# Fast_PLL_Page_2.net
KiCad netlist of a schematic drawn in Altium Designer
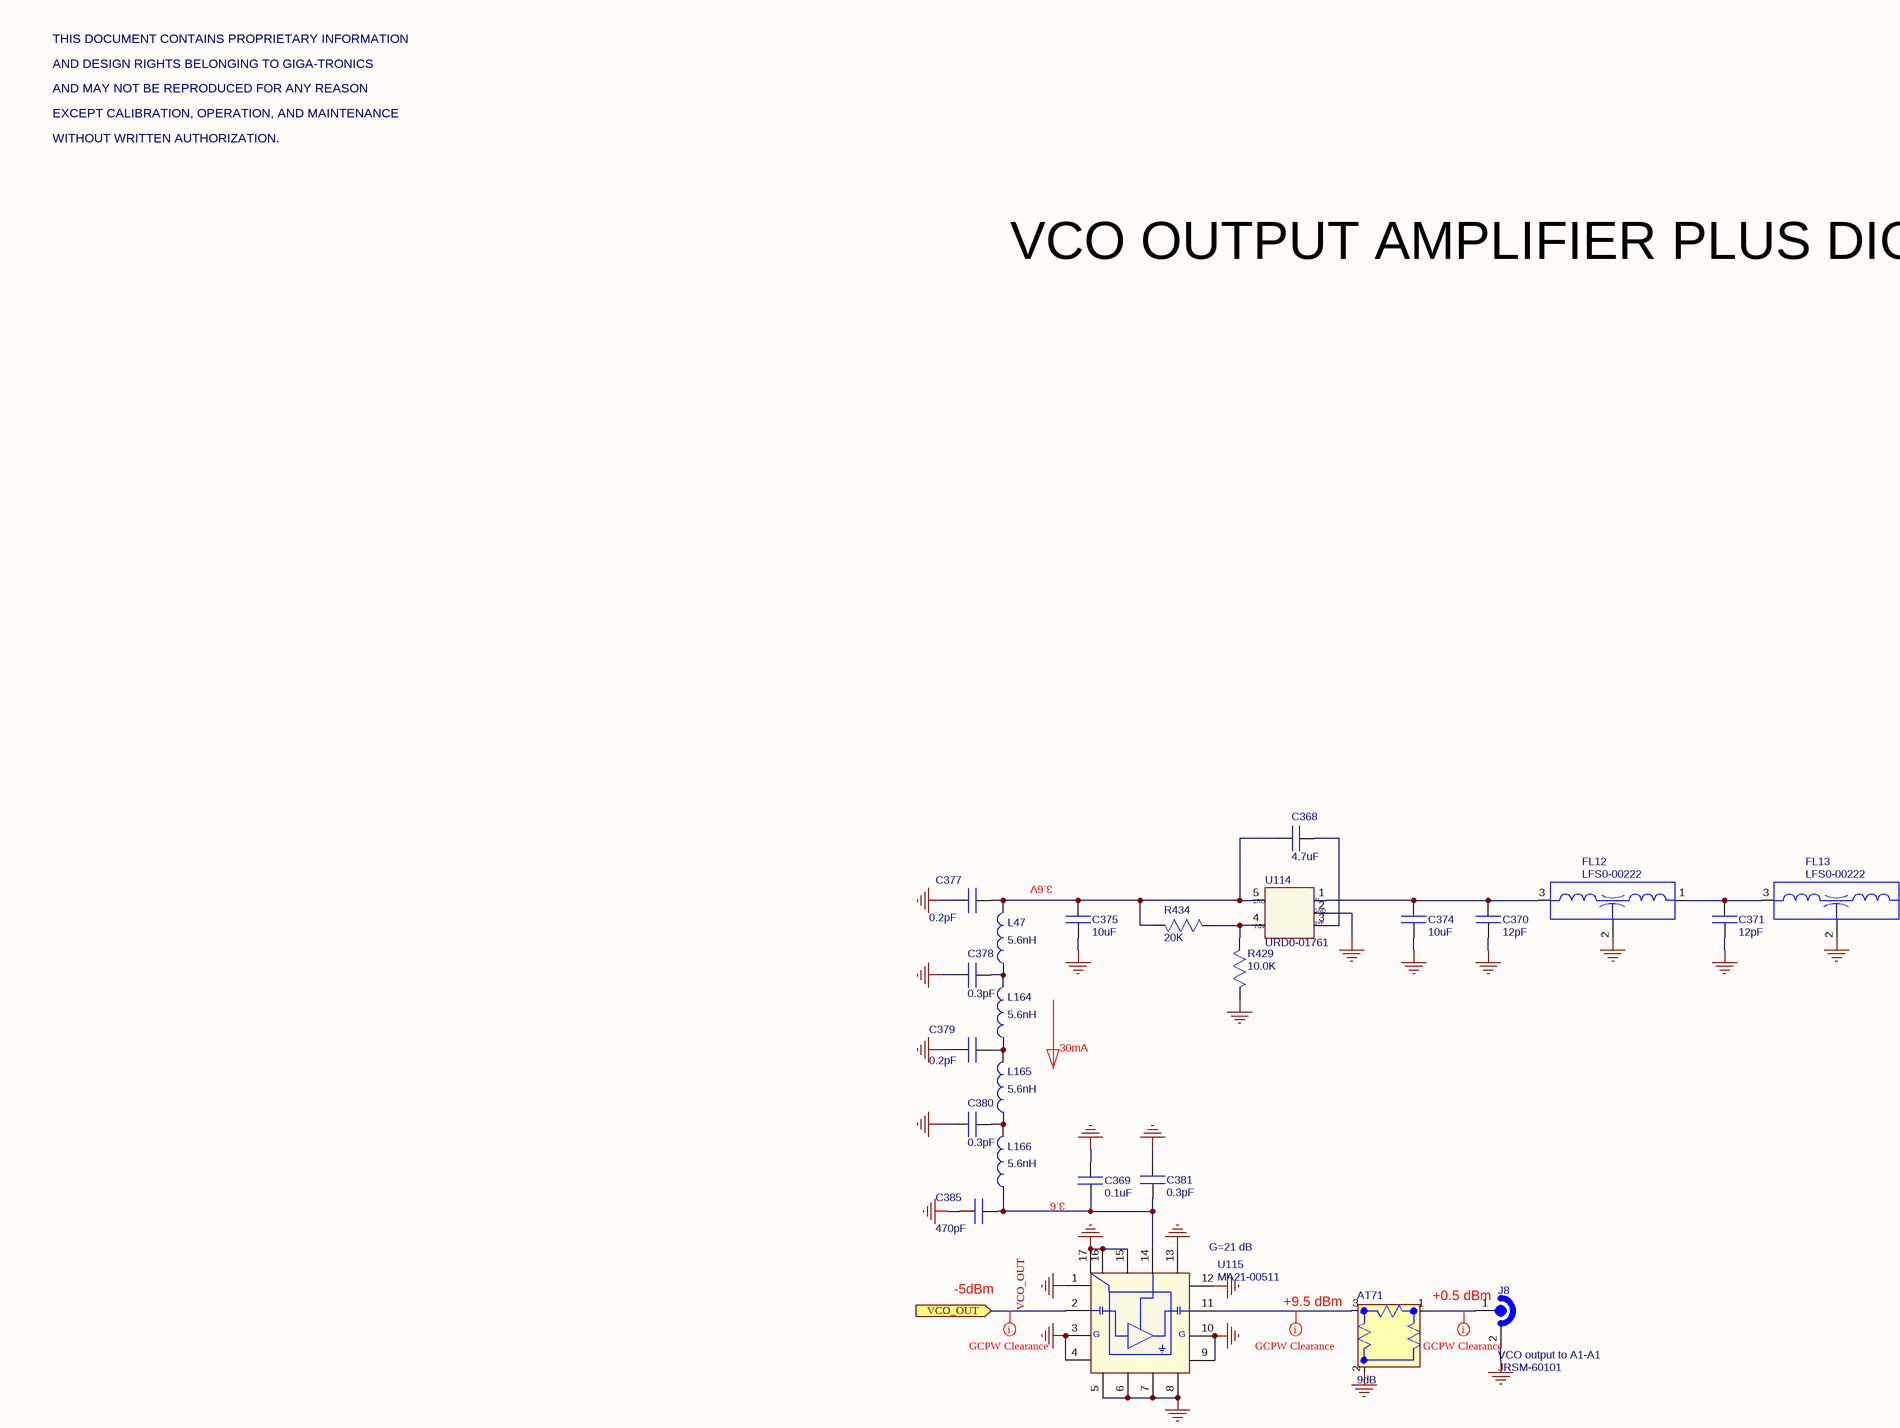
[diagram p0: Fast PLL Page 2.SchDoc, top left]
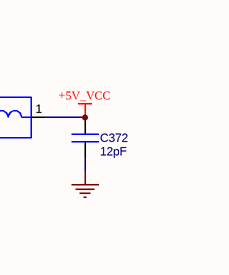
[diagram p1: Fast PLL Page 2.SchDoc, top right]
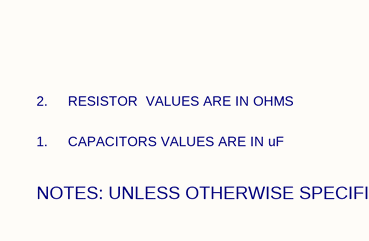
[diagram p2: Fast PLL Page 2.SchDoc, bottom left]
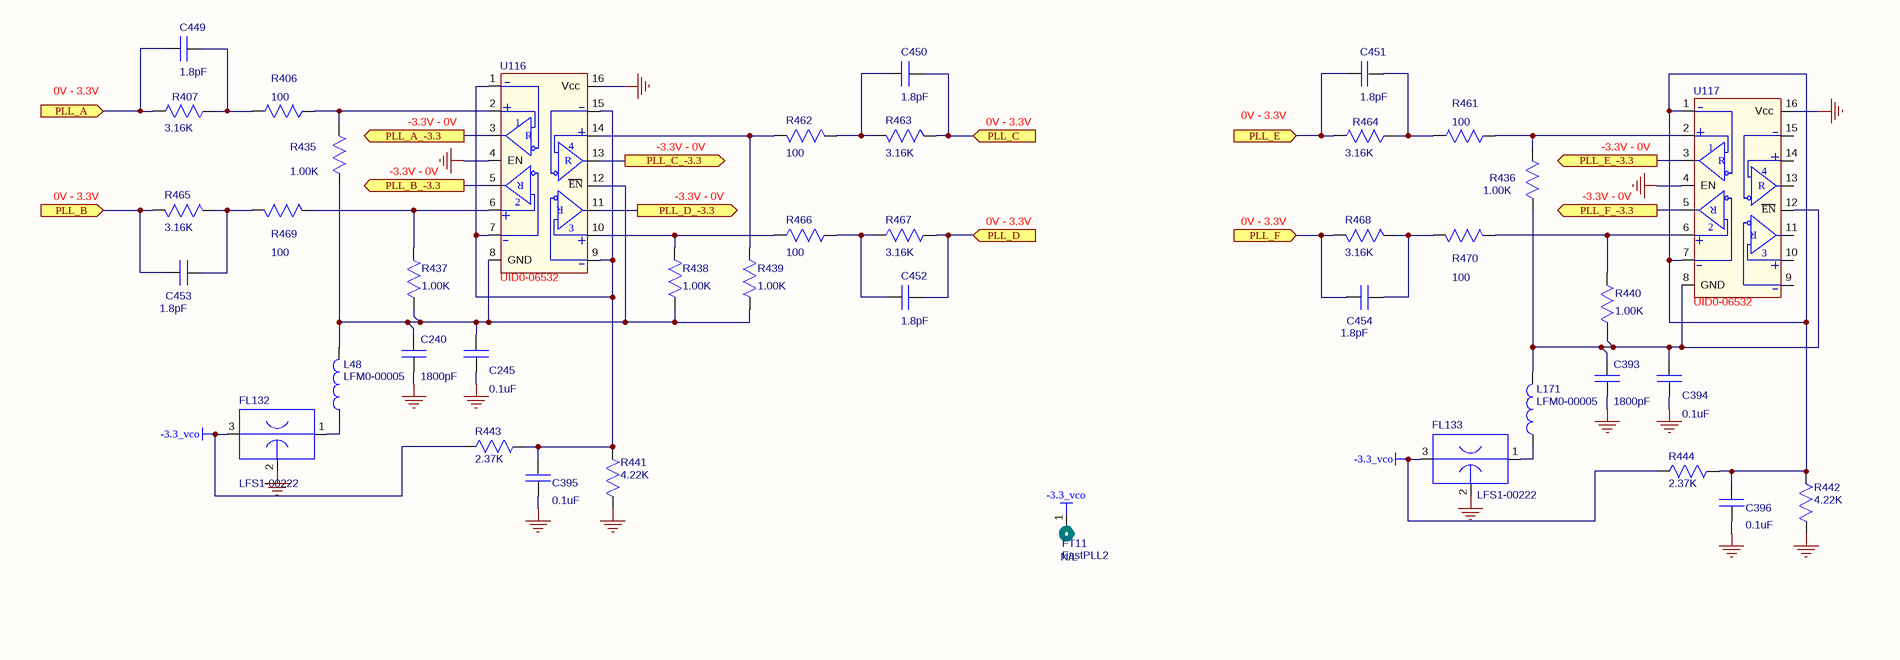
[diagram p3: Fast PLL Page 2.SchDoc, bottom right]

(export (version "E")
  (design (tool "Eeschema 10.0.6"))
  (components
    (comp (ref "AT71")
      (value "9dB")
      (footprint "ATTN-IMS-0805")
      (description "PAD;CHIP;9dB;+/-.3dB;.08 x .05;50 OHM;FACE DOWN")
      (fields (field (name "APPROVED") "CL"))
      (libsource (lib "Giga-tronics") (part "MPFC-A1009"))
    )
    (comp (ref "C240")
      (value "1800pF")
      (footprint "CAP-0402-N")
      (description "1800 PF;5%;X7R>50V;CHIP;0402")
      (fields (field (name "APPROVED") "CL"))
      (libsource (lib "Giga-tronics") (part "CK40-02180"))
    )
    (comp (ref "C245")
      (value "0.1uF")
      (footprint "CAP-0603-H035-N")
      (description ".1UF;10%;X7R;16V;CHIP;0603")
      (fields (field (name "APPROVED") "CL"))
      (libsource (lib "Giga-tronics") (part "CK45-04100"))
    )
    (comp (ref "C368")
      (value "4.7uF")
      (footprint "CAP-0805-N")
      (description "4.7uF 25V X5R CHIP CERAMIC")
      (fields (field (name "APPROVED") "CL"))
      (libsource (lib "Giga-tronics") (part "CK50-15470"))
    )
    (comp (ref "C369")
      (value "0.1uF")
      (footprint "CAP-0402-N")
      (description ".1 UF,10%;X7R;16V,CHIP;0402")
      (fields (field (name "APPROVED") "CL"))
      (libsource (lib "Giga-tronics") (part "CK40-04100"))
    )
    (comp (ref "C370")
      (value "12pF")
      (footprint "CAP-0402-N")
      (description "12 PF;5%;COG;>50V;CHIP;0402")
      (fields (field (name "APPROVED") "CL"))
      (libsource (lib "Giga-tronics") (part "CK40-00120"))
    )
    (comp (ref "C371")
      (value "12pF")
      (footprint "CAP-0402-N")
      (description "12 PF;5%;COG;>50V;CHIP;0402")
      (fields (field (name "APPROVED") "CL"))
      (libsource (lib "Giga-tronics") (part "CK40-00120"))
    )
    (comp (ref "C372")
      (value "12pF")
      (footprint "CAP-0402-N")
      (description "12 PF;5%;COG;>50V;CHIP;0402")
      (fields (field (name "APPROVED") "CL"))
      (libsource (lib "Giga-tronics") (part "CK40-00120"))
    )
    (comp (ref "C374")
      (value "10uF")
      (footprint "CAP-0805-N")
      (description "10uF 16V X5R CHIP CERAMIC")
      (fields (field (name "APPROVED") "CL"))
      (libsource (lib "Giga-tronics") (part "CK50-06100"))
    )
    (comp (ref "C375")
      (value "10uF")
      (footprint "CAP-0805-N")
      (description "10uF 16V X5R CHIP CERAMIC")
      (fields (field (name "APPROVED") "CL"))
      (libsource (lib "Giga-tronics") (part "CK50-06100"))
    )
    (comp (ref "C377")
      (value "0.2pF")
      (footprint "CAP-0402-RF")
      (description ".2 PF;200V;.05PF;HIGH Q;SMT;CERAMIC;0402")
      (fields (field (name "APPROVED") "CL"))
      (libsource (lib "Giga-tronics") (part "CK41-00002"))
    )
    (comp (ref "C378")
      (value "0.3pF")
      (footprint "CAP-0402-RF")
      (description ".3 PF 200V .05PF HIGH Q SMT 0402")
      (fields (field (name "APPROVED") "CL"))
      (libsource (lib "Giga-tronics") (part "CK41-00003"))
    )
    (comp (ref "C379")
      (value "0.2pF")
      (footprint "CAP-0402-RF")
      (description ".2 PF;200V;.05PF;HIGH Q;SMT;CERAMIC;0402")
      (fields (field (name "APPROVED") "CL"))
      (libsource (lib "Giga-tronics") (part "CK41-00002"))
    )
    (comp (ref "C380")
      (value "0.3pF")
      (footprint "CAP-0402-RF")
      (description ".3 PF 200V .05PF HIGH Q SMT 0402")
      (fields (field (name "APPROVED") "CL"))
      (libsource (lib "Giga-tronics") (part "CK41-00003"))
    )
    (comp (ref "C381")
      (value "0.3pF")
      (footprint "CAP-0402-RF")
      (description ".3 PF 200V .05PF HIGH Q SMT 0402")
      (fields (field (name "APPROVED") "CL"))
      (libsource (lib "Giga-tronics") (part "CK41-00003"))
    )
    (comp (ref "C385")
      (value "470pF")
      (footprint "CAP-0402-N")
      (description "470 PF;5%;COG;>50V;CHIP;0402")
      (fields (field (name "APPROVED") "CL"))
      (libsource (lib "Giga-tronics") (part "CK40-01470"))
    )
    (comp (ref "C393")
      (value "1800pF")
      (footprint "CAP-0402-N")
      (description "1800 PF;5%;X7R>50V;CHIP;0402")
      (fields (field (name "APPROVED") "CL"))
      (libsource (lib "Giga-tronics") (part "CK40-02180"))
    )
    (comp (ref "C394")
      (value "0.1uF")
      (footprint "CAP-0603-H035-N")
      (description ".1UF;10%;X7R;16V;CHIP;0603")
      (fields (field (name "APPROVED") "CL"))
      (libsource (lib "Giga-tronics") (part "CK45-04100"))
    )
    (comp (ref "C395")
      (value "0.1uF")
      (footprint "CAP-0603-H035-N")
      (description ".1UF;10%;X7R;16V;CHIP;0603")
      (fields (field (name "APPROVED") "CL"))
      (libsource (lib "Giga-tronics") (part "CK45-04100"))
    )
    (comp (ref "C396")
      (value "0.1uF")
      (footprint "CAP-0603-H035-N")
      (description ".1UF;10%;X7R;16V;CHIP;0603")
      (fields (field (name "APPROVED") "CL"))
      (libsource (lib "Giga-tronics") (part "CK45-04100"))
    )
    (comp (ref "C449")
      (value "1.8pF")
      (footprint "CAP-0402-N")
      (description "1.8pF;5%;COG;50V;CHIP;0402")
      (fields (field (name "APPROVED") "NM"))
      (libsource (lib "Giga-tronics") (part "CK40-00018"))
    )
    (comp (ref "C450")
      (value "1.8pF")
      (footprint "CAP-0402-N")
      (description "1.8pF;5%;COG;50V;CHIP;0402")
      (fields (field (name "APPROVED") "NM"))
      (libsource (lib "Giga-tronics") (part "CK40-00018"))
    )
    (comp (ref "C451")
      (value "1.8pF")
      (footprint "CAP-0402-N")
      (description "1.8pF;5%;COG;50V;CHIP;0402")
      (fields (field (name "APPROVED") "NM"))
      (libsource (lib "Giga-tronics") (part "CK40-00018"))
    )
    (comp (ref "C452")
      (value "1.8pF")
      (footprint "CAP-0402-N")
      (description "1.8pF;5%;COG;50V;CHIP;0402")
      (fields (field (name "APPROVED") "NM"))
      (libsource (lib "Giga-tronics") (part "CK40-00018"))
    )
    (comp (ref "C453")
      (value "1.8pF")
      (footprint "CAP-0402-N")
      (description "1.8pF;5%;COG;50V;CHIP;0402")
      (fields (field (name "APPROVED") "NM"))
      (libsource (lib "Giga-tronics") (part "CK40-00018"))
    )
    (comp (ref "C454")
      (value "1.8pF")
      (footprint "CAP-0402-N")
      (description "1.8pF;5%;COG;50V;CHIP;0402")
      (fields (field (name "APPROVED") "NM"))
      (libsource (lib "Giga-tronics") (part "CK40-00018"))
    )
    (comp (ref "FL12")
      (value "Filter EMI 2200PF,1206")
      (footprint "FIL-NFE31P-1206-4P")
      (fields (field (name "G_PN") "LFS0-00222") (field (name "APPROVED") "CL"))
      (libsource (lib "Giga-tronics") (part "LFS0-00222"))
    )
    (comp (ref "FL13")
      (value "Filter EMI 2200PF,1206")
      (footprint "FIL-NFE31P-1206-4P")
      (fields (field (name "G_PN") "LFS0-00222") (field (name "APPROVED") "CL"))
      (libsource (lib "Giga-tronics") (part "LFS0-00222"))
    )
    (comp (ref "FL132")
      (value "NFM18CC222R1C3")
      (footprint "FIL-NFL18C")
      (description "2200 PF FEED THRU FILTER 0603")
      (fields (field (name "G_PN") "LFS1-00222") (field (name "APPROVED") "NM"))
      (libsource (lib "Giga-tronics") (part "LFS1-00222"))
    )
    (comp (ref "FL133")
      (value "NFM18CC222R1C3")
      (footprint "FIL-NFL18C")
      (description "2200 PF FEED THRU FILTER 0603")
      (fields (field (name "G_PN") "LFS1-00222") (field (name "APPROVED") "NM"))
      (libsource (lib "Giga-tronics") (part "LFS1-00222"))
    )
    (comp (ref "FT11")
      (value "FastPLL2")
      (footprint "FromToNode_ML2")
      (fields (field (name "NOLOAD") "N/L") (field (name "APPROVED") "*"))
      (libsource (lib "Giga-tronics") (part "FromToNode"))
    )
    (comp (ref "J8")
      (value "VCO output to A1-A1")
      (footprint "JRSM-60101")
      (description "SMPM SM MALE,STRAIGHT SMT, R/A COPLANAR, 4 PIN THRU-HOLE")
      (fields (field (name "G_PN") "JRSM-60101") (field (name "APPROVED") "CL"))
      (libsource (lib "Giga-tronics") (part "JRSM-60101"))
    )
    (comp (ref "L47")
      (value "5.6nH")
      (footprint "IND-0402HP")
      (description "INDUCTOR;5.6NH;2%;6.6GHZ SRF;105Q @1.7GHZ;.048 DCR;1.6A;0402")
      (fields (field (name "APPROVED") "CL"))
      (libsource (lib "Giga-tronics") (part "LSA6-02560"))
    )
    (comp (ref "L48")
      (value "EMI FILTER;CHIP;330 OHMS@100MHZ;0.5A;0.30 DCR;0603")
      (footprint "BLM18A_Murata")
      (fields (field (name "G_PN") "LFM0-00005") (field (name "APPROVED") "NM"))
      (libsource (lib "Giga-tronics") (part "LFM0-00005"))
    )
    (comp (ref "L164")
      (value "5.6nH")
      (footprint "IND-0402HP")
      (description "INDUCTOR;5.6NH;2%;6.6GHZ SRF;105Q @1.7GHZ;.048 DCR;1.6A;0402")
      (fields (field (name "APPROVED") "CL"))
      (libsource (lib "Giga-tronics") (part "LSA6-02560"))
    )
    (comp (ref "L165")
      (value "5.6nH")
      (footprint "IND-0402HP")
      (description "INDUCTOR;5.6NH;2%;6.6GHZ SRF;105Q @1.7GHZ;.048 DCR;1.6A;0402")
      (fields (field (name "APPROVED") "CL"))
      (libsource (lib "Giga-tronics") (part "LSA6-02560"))
    )
    (comp (ref "L166")
      (value "5.6nH")
      (footprint "IND-0402HP")
      (description "INDUCTOR;5.6NH;2%;6.6GHZ SRF;105Q @1.7GHZ;.048 DCR;1.6A;0402")
      (fields (field (name "APPROVED") "CL"))
      (libsource (lib "Giga-tronics") (part "LSA6-02560"))
    )
    (comp (ref "L171")
      (value "EMI FILTER;CHIP;330 OHMS@100MHZ;0.5A;0.30 DCR;0603")
      (footprint "BLM18A_Murata")
      (fields (field (name "G_PN") "LFM0-00005") (field (name "APPROVED") "NM"))
      (libsource (lib "Giga-tronics") (part "LFM0-00005"))
    )
    (comp (ref "R406")
      (value "100")
      (footprint "RES-0402-N")
      (description "100 OHMS; 1%; .1W; 100PPM; FILM; CHIP; 0402")
      (fields (field (name "APPROVED") "CL"))
      (libsource (lib "Giga-tronics") (part "RK35-01000"))
    )
    (comp (ref "R407")
      (value "3.16K")
      (footprint "RES-0402-N")
      (description "3.16K OHMS;.06W;1%;200PPM;FILM;CHIP;0402")
      (fields (field (name "APPROVED") "CL"))
      (libsource (lib "Giga-tronics") (part "RK35-13160"))
    )
    (comp (ref "R429")
      (value "10.0K")
      (footprint "RES-0402-N")
      (description "10.0K OHMS;.06W;1%;200PPM;FILM;CHIP;0402")
      (fields (field (name "APPROVED") "CL"))
      (libsource (lib "Giga-tronics") (part "RK35-21000"))
    )
    (comp (ref "R434")
      (value "20K")
      (footprint "RES-0402-N")
      (description "20K OHMS;.06W;1%;100PPM;FILM;CHIP;0402")
      (fields (field (name "APPROVED") "CL"))
      (libsource (lib "Giga-tronics") (part "RK35-22000"))
    )
    (comp (ref "R435")
      (value "1.00K")
      (footprint "RES-0402-N")
      (description "1.0K OHMS;.06W;1%;200PPM;FILM;CHIP;0402")
      (fields (field (name "APPROVED") "CL"))
      (libsource (lib "Giga-tronics") (part "RK35-11000"))
    )
    (comp (ref "R436")
      (value "1.00K")
      (footprint "RES-0402-N")
      (description "1.0K OHMS;.06W;1%;200PPM;FILM;CHIP;0402")
      (fields (field (name "APPROVED") "CL"))
      (libsource (lib "Giga-tronics") (part "RK35-11000"))
    )
    (comp (ref "R437")
      (value "1.00K")
      (footprint "RES-0402-N")
      (description "1.0K OHMS;.06W;1%;200PPM;FILM;CHIP;0402")
      (fields (field (name "APPROVED") "CL"))
      (libsource (lib "Giga-tronics") (part "RK35-11000"))
    )
    (comp (ref "R438")
      (value "1.00K")
      (footprint "RES-0402-N")
      (description "1.0K OHMS;.06W;1%;200PPM;FILM;CHIP;0402")
      (fields (field (name "APPROVED") "CL"))
      (libsource (lib "Giga-tronics") (part "RK35-11000"))
    )
    (comp (ref "R439")
      (value "1.00K")
      (footprint "RES-0402-N")
      (description "1.0K OHMS;.06W;1%;200PPM;FILM;CHIP;0402")
      (fields (field (name "APPROVED") "CL"))
      (libsource (lib "Giga-tronics") (part "RK35-11000"))
    )
    (comp (ref "R440")
      (value "1.00K")
      (footprint "RES-0402-N")
      (description "1.0K OHMS;.06W;1%;200PPM;FILM;CHIP;0402")
      (fields (field (name "APPROVED") "CL"))
      (libsource (lib "Giga-tronics") (part "RK35-11000"))
    )
    (comp (ref "R441")
      (value "4.22K")
      (footprint "RES-0402-N")
      (description "4.22K OHMS;.06W;1%;200PPM;FILM;CHIP;0402")
      (fields (field (name "APPROVED") "CL"))
      (libsource (lib "Giga-tronics") (part "RK35-14220"))
    )
    (comp (ref "R442")
      (value "4.22K")
      (footprint "RES-0402-N")
      (description "4.22K OHMS;.06W;1%;200PPM;FILM;CHIP;0402")
      (fields (field (name "APPROVED") "CL"))
      (libsource (lib "Giga-tronics") (part "RK35-14220"))
    )
    (comp (ref "R443")
      (value "2.37K")
      (footprint "RES-0402-N")
      (description "2.37K OHMS;.06W;1%;200PPM;FILM;CHIP;0402")
      (fields (field (name "APPROVED") "CL"))
      (libsource (lib "Giga-tronics") (part "RK35-12370"))
    )
    (comp (ref "R444")
      (value "2.37K")
      (footprint "RES-0402-N")
      (description "2.37K OHMS;.06W;1%;200PPM;FILM;CHIP;0402")
      (fields (field (name "APPROVED") "CL"))
      (libsource (lib "Giga-tronics") (part "RK35-12370"))
    )
    (comp (ref "R461")
      (value "100")
      (footprint "RES-0402-N")
      (description "100 OHMS; 1%; .1W; 100PPM; FILM; CHIP; 0402")
      (fields (field (name "APPROVED") "CL"))
      (libsource (lib "Giga-tronics") (part "RK35-01000"))
    )
    (comp (ref "R462")
      (value "100")
      (footprint "RES-0402-N")
      (description "100 OHMS; 1%; .1W; 100PPM; FILM; CHIP; 0402")
      (fields (field (name "APPROVED") "CL"))
      (libsource (lib "Giga-tronics") (part "RK35-01000"))
    )
    (comp (ref "R463")
      (value "3.16K")
      (footprint "RES-0402-N")
      (description "3.16K OHMS;.06W;1%;200PPM;FILM;CHIP;0402")
      (fields (field (name "APPROVED") "CL"))
      (libsource (lib "Giga-tronics") (part "RK35-13160"))
    )
    (comp (ref "R464")
      (value "3.16K")
      (footprint "RES-0402-N")
      (description "3.16K OHMS;.06W;1%;200PPM;FILM;CHIP;0402")
      (fields (field (name "APPROVED") "CL"))
      (libsource (lib "Giga-tronics") (part "RK35-13160"))
    )
    (comp (ref "R465")
      (value "3.16K")
      (footprint "RES-0402-N")
      (description "3.16K OHMS;.06W;1%;200PPM;FILM;CHIP;0402")
      (fields (field (name "APPROVED") "CL"))
      (libsource (lib "Giga-tronics") (part "RK35-13160"))
    )
    (comp (ref "R466")
      (value "100")
      (footprint "RES-0402-N")
      (description "100 OHMS; 1%; .1W; 100PPM; FILM; CHIP; 0402")
      (fields (field (name "APPROVED") "CL"))
      (libsource (lib "Giga-tronics") (part "RK35-01000"))
    )
    (comp (ref "R467")
      (value "3.16K")
      (footprint "RES-0402-N")
      (description "3.16K OHMS;.06W;1%;200PPM;FILM;CHIP;0402")
      (fields (field (name "APPROVED") "CL"))
      (libsource (lib "Giga-tronics") (part "RK35-13160"))
    )
    (comp (ref "R468")
      (value "3.16K")
      (footprint "RES-0402-N")
      (description "3.16K OHMS;.06W;1%;200PPM;FILM;CHIP;0402")
      (fields (field (name "APPROVED") "CL"))
      (libsource (lib "Giga-tronics") (part "RK35-13160"))
    )
    (comp (ref "R469")
      (value "100")
      (footprint "RES-0402-N")
      (description "100 OHMS; 1%; .1W; 100PPM; FILM; CHIP; 0402")
      (fields (field (name "APPROVED") "CL"))
      (libsource (lib "Giga-tronics") (part "RK35-01000"))
    )
    (comp (ref "R470")
      (value "100")
      (footprint "RES-0402-N")
      (description "100 OHMS; 1%; .1W; 100PPM; FILM; CHIP; 0402")
      (fields (field (name "APPROVED") "CL"))
      (libsource (lib "Giga-tronics") (part "RK35-01000"))
    )
    (comp (ref "U114")
      (value "LT1761ES5-BYP;1.8V-20V IN;100mA;LOW NOISE;SOT-23-5")
      (footprint "SOT23-5_LINEAR")
      (fields (field (name "G_PN") "URD0-01761") (field (name "APPROVED") "CL"))
      (libsource (lib "Giga-tronics") (part "URD0-01761"))
    )
    (comp (ref "U115")
      (value "AMP;5-11GHz;21dB;+10dBm;3.6V;30mA;QFN-16")
      (footprint "QFN-16_C-MMIC")
      (fields (field (name "G_PN") "MA21-00511") (field (name "APPROVED") "CL"))
      (libsource (lib "Giga-tronics") (part "MA21-00511"))
    )
    (comp (ref "U116")
      (value "UID0-06532")
      (footprint "Hydra_Ref_A1-A3:MTC16")
      (description "SN65LVDS32PW 3.3V LVDS Receiver 16 Pin TSSOP")
      (fields (field (name "APPROVED") "CL"))
      (libsource (lib "Giga-tronics") (part "UID0-06532"))
    )
    (comp (ref "U117")
      (value "UID0-06532")
      (footprint "Hydra_Ref_A1-A3:MTC16")
      (description "SN65LVDS32PW 3.3V LVDS Receiver 16 Pin TSSOP")
      (fields (field (name "APPROVED") "CL"))
      (libsource (lib "Giga-tronics") (part "UID0-06532"))
    )
  )
  (nets
    (net (code "1") (name "+5V_VCC") (class "Default")
      (node (ref "C372") (pin "2") (pintype "passive"))
      (node (ref "FL13") (pin "1") (pinfunction "IN_1") (pintype "passive"))
    )
    (net (code "2") (name "-3.3_vco") (class "Default")
      (node (ref "FL132") (pin "3") (pintype "passive"))
      (node (ref "FL133") (pin "3") (pintype "passive"))
      (node (ref "FT11") (pin "1") (pinfunction "1_1") (pintype "passive"))
      (node (ref "R443") (pin "2") (pintype "passive"))
      (node (ref "R444") (pin "2") (pintype "passive"))
    )
    (net (code "3") (name "/PLL_A") (class "Default")
      (node (ref "C449") (pin "1") (pintype "passive"))
      (node (ref "R407") (pin "1") (pintype "passive"))
    )
    (net (code "4") (name "/PLL_A_-3.3") (class "Default")
      (node (ref "U116") (pin "3") (pinfunction "Rout1_3") (pintype "passive"))
    )
    (net (code "5") (name "/PLL_B") (class "Default")
      (node (ref "C453") (pin "1") (pintype "passive"))
      (node (ref "R465") (pin "1") (pintype "passive"))
    )
    (net (code "6") (name "/PLL_B_-3.3") (class "Default")
      (node (ref "U116") (pin "5") (pinfunction "Rout2_5") (pintype "passive"))
    )
    (net (code "7") (name "/PLL_C") (class "Default")
      (node (ref "C450") (pin "1") (pintype "passive"))
      (node (ref "R463") (pin "1") (pintype "passive"))
    )
    (net (code "8") (name "/PLL_C_-3.3") (class "Default")
      (node (ref "U116") (pin "13") (pinfunction "Rout4_13") (pintype "passive"))
    )
    (net (code "9") (name "/PLL_D") (class "Default")
      (node (ref "C452") (pin "1") (pintype "passive"))
      (node (ref "R467") (pin "1") (pintype "passive"))
    )
    (net (code "10") (name "/PLL_D_-3.3") (class "Default")
      (node (ref "U116") (pin "11") (pinfunction "Rout3_11") (pintype "passive"))
    )
    (net (code "11") (name "/PLL_E") (class "Default")
      (node (ref "C451") (pin "1") (pintype "passive"))
      (node (ref "R464") (pin "1") (pintype "passive"))
    )
    (net (code "12") (name "/PLL_E_-3.3") (class "Default")
      (node (ref "U117") (pin "3") (pinfunction "Rout1_3") (pintype "passive"))
    )
    (net (code "13") (name "/PLL_F") (class "Default")
      (node (ref "C454") (pin "1") (pintype "passive"))
      (node (ref "R468") (pin "1") (pintype "passive"))
    )
    (net (code "14") (name "/PLL_F_-3.3") (class "Default")
      (node (ref "U117") (pin "5") (pinfunction "Rout2_5") (pintype "passive"))
    )
    (net (code "15") (name "/VCO_OUT") (class "Default")
      (node (ref "U115") (pin "2") (pinfunction "RF_IN_2") (pintype "passive"))
    )
    (net (code "16") (name "GND") (class "Default")
      (node (ref "AT71") (pin "2") (pinfunction "GND_2") (pintype "power_in"))
      (node (ref "C240") (pin "1") (pintype "passive"))
      (node (ref "C245") (pin "1") (pintype "passive"))
      (node (ref "C369") (pin "2") (pintype "passive"))
      (node (ref "C370") (pin "1") (pintype "passive"))
      (node (ref "C371") (pin "1") (pintype "passive"))
      (node (ref "C372") (pin "1") (pintype "passive"))
      (node (ref "C374") (pin "1") (pintype "passive"))
      (node (ref "C375") (pin "1") (pintype "passive"))
      (node (ref "C377") (pin "1") (pintype "passive"))
      (node (ref "C378") (pin "1") (pintype "passive"))
      (node (ref "C379") (pin "1") (pintype "passive"))
      (node (ref "C380") (pin "1") (pintype "passive"))
      (node (ref "C381") (pin "1") (pintype "passive"))
      (node (ref "C385") (pin "2") (pintype "passive"))
      (node (ref "C393") (pin "1") (pintype "passive"))
      (node (ref "C394") (pin "1") (pintype "passive"))
      (node (ref "C395") (pin "1") (pintype "passive"))
      (node (ref "C396") (pin "1") (pintype "passive"))
      (node (ref "FL12") (pin "2") (pinfunction "GND_2") (pintype "passive"))
      (node (ref "FL13") (pin "2") (pinfunction "GND_2") (pintype "passive"))
      (node (ref "FL132") (pin "2") (pintype "passive"))
      (node (ref "FL133") (pin "2") (pintype "passive"))
      (node (ref "J8") (pin "2") (pinfunction "GND_2") (pintype "passive"))
      (node (ref "R429") (pin "1") (pintype "passive"))
      (node (ref "R441") (pin "1") (pintype "passive"))
      (node (ref "R442") (pin "1") (pintype "passive"))
      (node (ref "U114") (pin "2") (pinfunction "GND_2") (pintype "passive"))
      (node (ref "U115") (pin "1") (pinfunction "NC_1") (pintype "passive"))
      (node (ref "U115") (pin "10") (pinfunction "GND_10") (pintype "passive"))
      (node (ref "U115") (pin "12") (pinfunction "NC_12") (pintype "passive"))
      (node (ref "U115") (pin "13") (pinfunction "NC_13") (pintype "passive"))
      (node (ref "U115") (pin "15") (pinfunction "NC_15") (pintype "passive"))
      (node (ref "U115") (pin "16") (pinfunction "NC_16") (pintype "passive"))
      (node (ref "U115") (pin "17") (pinfunction "GND_17") (pintype "passive"))
      (node (ref "U115") (pin "3") (pinfunction "GND_3") (pintype "passive"))
      (node (ref "U115") (pin "4") (pinfunction "NC_4") (pintype "passive"))
      (node (ref "U115") (pin "5") (pinfunction "NC_5") (pintype "passive"))
      (node (ref "U115") (pin "6") (pinfunction "NC_6") (pintype "passive"))
      (node (ref "U115") (pin "7") (pinfunction "NC_7") (pintype "passive"))
      (node (ref "U115") (pin "8") (pinfunction "NC_8") (pintype "passive"))
      (node (ref "U115") (pin "9") (pinfunction "NC_9") (pintype "passive"))
      (node (ref "U116") (pin "16") (pinfunction "Vcc_16") (pintype "power_in"))
      (node (ref "U116") (pin "4") (pinfunction "EN_4") (pintype "passive"))
      (node (ref "U117") (pin "16") (pinfunction "Vcc_16") (pintype "power_in"))
      (node (ref "U117") (pin "4") (pinfunction "EN_4") (pintype "passive"))
    )
    (net (code "17") (name "Net-(C378-Pad2)") (class "Default")
      (node (ref "C378") (pin "2") (pintype "passive"))
      (node (ref "L164") (pin "2") (pinfunction "2_2") (pintype "passive"))
      (node (ref "L47") (pin "1") (pinfunction "1_1") (pintype "passive"))
    )
    (net (code "18") (name "Net-(C379-Pad2)") (class "Default")
      (node (ref "C379") (pin "2") (pintype "passive"))
      (node (ref "L164") (pin "1") (pinfunction "1_1") (pintype "passive"))
      (node (ref "L165") (pin "2") (pinfunction "2_2") (pintype "passive"))
    )
    (net (code "19") (name "Net-(C380-Pad2)") (class "Default")
      (node (ref "C380") (pin "2") (pintype "passive"))
      (node (ref "L165") (pin "1") (pinfunction "1_1") (pintype "passive"))
      (node (ref "L166") (pin "2") (pinfunction "2_2") (pintype "passive"))
    )
    (net (code "20") (name "Net-(C449-Pad2)") (class "Default")
      (node (ref "C449") (pin "2") (pintype "passive"))
      (node (ref "R406") (pin "1") (pintype "passive"))
      (node (ref "R407") (pin "2") (pintype "passive"))
    )
    (net (code "21") (name "Net-(C450-Pad2)") (class "Default")
      (node (ref "C450") (pin "2") (pintype "passive"))
      (node (ref "R462") (pin "1") (pintype "passive"))
      (node (ref "R463") (pin "2") (pintype "passive"))
    )
    (net (code "22") (name "Net-(C451-Pad2)") (class "Default")
      (node (ref "C451") (pin "2") (pintype "passive"))
      (node (ref "R461") (pin "1") (pintype "passive"))
      (node (ref "R464") (pin "2") (pintype "passive"))
    )
    (net (code "23") (name "Net-(C452-Pad2)") (class "Default")
      (node (ref "C452") (pin "2") (pintype "passive"))
      (node (ref "R466") (pin "1") (pintype "passive"))
      (node (ref "R467") (pin "2") (pintype "passive"))
    )
    (net (code "24") (name "Net-(C453-Pad2)") (class "Default")
      (node (ref "C453") (pin "2") (pintype "passive"))
      (node (ref "R465") (pin "2") (pintype "passive"))
      (node (ref "R469") (pin "1") (pintype "passive"))
    )
    (net (code "25") (name "Net-(C454-Pad2)") (class "Default")
      (node (ref "C454") (pin "2") (pintype "passive"))
      (node (ref "R468") (pin "2") (pintype "passive"))
      (node (ref "R470") (pin "1") (pintype "passive"))
    )
    (net (code "26") (name "Net-(FL12-IN)") (class "Default")
      (node (ref "C371") (pin "2") (pintype "passive"))
      (node (ref "FL12") (pin "1") (pinfunction "IN_1") (pintype "passive"))
      (node (ref "FL13") (pin "3") (pinfunction "OUT_3") (pintype "passive"))
    )
    (net (code "27") (name "Net-(FL12-OUT)") (class "Default")
      (node (ref "C370") (pin "2") (pintype "passive"))
      (node (ref "C374") (pin "2") (pintype "passive"))
      (node (ref "FL12") (pin "3") (pinfunction "OUT_3") (pintype "passive"))
      (node (ref "U114") (pin "1") (pinfunction "IN_1") (pintype "passive"))
    )
    (net (code "28") (name "Net-(FL132-Pad1)") (class "Default")
      (node (ref "FL132") (pin "1") (pintype "passive"))
      (node (ref "L48") (pin "2") (pintype "passive"))
    )
    (net (code "29") (name "Net-(FL133-Pad1)") (class "Default")
      (node (ref "FL133") (pin "1") (pintype "passive"))
      (node (ref "L171") (pin "2") (pintype "passive"))
    )
    (net (code "30") (name "Net-(J8-CNTR)") (class "Default")
      (node (ref "AT71") (pin "1") (pinfunction "IN/OUT_1") (pintype "passive"))
      (node (ref "J8") (pin "1") (pinfunction "CNTR_1") (pintype "passive"))
    )
    (net (code "31") (name "Net-(U114-ADJ)") (class "Default")
      (node (ref "R429") (pin "2") (pintype "passive"))
      (node (ref "R434") (pin "2") (pintype "passive"))
      (node (ref "U114") (pin "4") (pinfunction "ADJ_4") (pintype "passive"))
    )
    (net (code "32") (name "Net-(U114-BYP)") (class "Default")
      (node (ref "C368") (pin "1") (pintype "passive"))
      (node (ref "U114") (pin "3") (pinfunction "BYP_3") (pintype "passive"))
    )
    (net (code "33") (name "Net-(U114-OUT)") (class "Default")
      (node (ref "C368") (pin "2") (pintype "passive"))
      (node (ref "C375") (pin "2") (pintype "passive"))
      (node (ref "C377") (pin "2") (pintype "passive"))
      (node (ref "L47") (pin "2") (pinfunction "2_2") (pintype "passive"))
      (node (ref "R434") (pin "1") (pintype "passive"))
      (node (ref "U114") (pin "5") (pinfunction "OUT_5") (pintype "passive"))
    )
    (net (code "34") (name "Net-(U115-RF_OUT)") (class "Default")
      (node (ref "AT71") (pin "3") (pinfunction "IN/OUT_3") (pintype "passive"))
      (node (ref "U115") (pin "11") (pinfunction "RF_OUT_11") (pintype "passive"))
    )
    (net (code "35") (name "Net-(U115-Vdd)") (class "Default")
      (node (ref "C369") (pin "1") (pintype "passive"))
      (node (ref "C381") (pin "2") (pintype "passive"))
      (node (ref "C385") (pin "1") (pintype "passive"))
      (node (ref "L166") (pin "1") (pinfunction "1_1") (pintype "passive"))
      (node (ref "U115") (pin "14") (pinfunction "Vdd_14") (pintype "passive"))
    )
    (net (code "36") (name "Net-(U116-EN_Rev)") (class "Default")
      (node (ref "C240") (pin "2") (pintype "passive"))
      (node (ref "C245") (pin "2") (pintype "passive"))
      (node (ref "L48") (pin "1") (pintype "passive"))
      (node (ref "R435") (pin "1") (pintype "passive"))
      (node (ref "R437") (pin "1") (pintype "passive"))
      (node (ref "R438") (pin "2") (pintype "passive"))
      (node (ref "R439") (pin "2") (pintype "passive"))
      (node (ref "U116") (pin "12") (pinfunction "EN_Rev_12") (pintype "passive"))
      (node (ref "U116") (pin "8") (pinfunction "GND_8") (pintype "power_in"))
    )
    (net (code "37") (name "Net-(U116-Rin1+)") (class "Default")
      (node (ref "R406") (pin "2") (pintype "passive"))
      (node (ref "R435") (pin "2") (pintype "passive"))
      (node (ref "U116") (pin "2") (pinfunction "Rin1+_2") (pintype "passive"))
    )
    (net (code "38") (name "Net-(U116-Rin1-)") (class "Default")
      (node (ref "C395") (pin "2") (pintype "passive"))
      (node (ref "R441") (pin "2") (pintype "passive"))
      (node (ref "R443") (pin "1") (pintype "passive"))
      (node (ref "U116") (pin "1") (pinfunction "Rin1-_1") (pintype "passive"))
      (node (ref "U116") (pin "15") (pinfunction "Rin4-_15") (pintype "passive"))
      (node (ref "U116") (pin "7") (pinfunction "Rin2-_7") (pintype "passive"))
      (node (ref "U116") (pin "9") (pinfunction "Rin3-_9") (pintype "passive"))
    )
    (net (code "39") (name "Net-(U116-Rin2+)") (class "Default")
      (node (ref "R437") (pin "2") (pintype "passive"))
      (node (ref "R469") (pin "2") (pintype "passive"))
      (node (ref "U116") (pin "6") (pinfunction "Rin2+_6") (pintype "passive"))
    )
    (net (code "40") (name "Net-(U116-Rin3+)") (class "Default")
      (node (ref "R438") (pin "1") (pintype "passive"))
      (node (ref "R466") (pin "2") (pintype "passive"))
      (node (ref "U116") (pin "10") (pinfunction "Rin3+_10") (pintype "passive"))
    )
    (net (code "41") (name "Net-(U116-Rin4+)") (class "Default")
      (node (ref "R439") (pin "1") (pintype "passive"))
      (node (ref "R462") (pin "2") (pintype "passive"))
      (node (ref "U116") (pin "14") (pinfunction "Rin4+_14") (pintype "passive"))
    )
    (net (code "42") (name "Net-(U117-EN_Rev)") (class "Default")
      (node (ref "C393") (pin "2") (pintype "passive"))
      (node (ref "C394") (pin "2") (pintype "passive"))
      (node (ref "L171") (pin "1") (pintype "passive"))
      (node (ref "R436") (pin "1") (pintype "passive"))
      (node (ref "R440") (pin "1") (pintype "passive"))
      (node (ref "U117") (pin "12") (pinfunction "EN_Rev_12") (pintype "passive"))
      (node (ref "U117") (pin "8") (pinfunction "GND_8") (pintype "power_in"))
    )
    (net (code "43") (name "Net-(U117-Rin1+)") (class "Default")
      (node (ref "R436") (pin "2") (pintype "passive"))
      (node (ref "R461") (pin "2") (pintype "passive"))
      (node (ref "U117") (pin "2") (pinfunction "Rin1+_2") (pintype "passive"))
    )
    (net (code "44") (name "Net-(U117-Rin1-)") (class "Default")
      (node (ref "C396") (pin "2") (pintype "passive"))
      (node (ref "R442") (pin "2") (pintype "passive"))
      (node (ref "R444") (pin "1") (pintype "passive"))
      (node (ref "U117") (pin "1") (pinfunction "Rin1-_1") (pintype "passive"))
      (node (ref "U117") (pin "7") (pinfunction "Rin2-_7") (pintype "passive"))
    )
    (net (code "45") (name "Net-(U117-Rin2+)") (class "Default")
      (node (ref "R440") (pin "2") (pintype "passive"))
      (node (ref "R470") (pin "2") (pintype "passive"))
      (node (ref "U117") (pin "6") (pinfunction "Rin2+_6") (pintype "passive"))
    )
    (net (code "46") (name "unconnected-(U117-Rin3+-Pad10)") (class "Default")
      (node (ref "U117") (pin "10") (pinfunction "Rin3+_10") (pintype "passive"))
    )
    (net (code "47") (name "unconnected-(U117-Rin3--Pad9)") (class "Default")
      (node (ref "U117") (pin "9") (pinfunction "Rin3-_9") (pintype "passive"))
    )
    (net (code "48") (name "unconnected-(U117-Rin4+-Pad14)") (class "Default")
      (node (ref "U117") (pin "14") (pinfunction "Rin4+_14") (pintype "passive"))
    )
    (net (code "49") (name "unconnected-(U117-Rin4--Pad15)") (class "Default")
      (node (ref "U117") (pin "15") (pinfunction "Rin4-_15") (pintype "passive"))
    )
    (net (code "50") (name "unconnected-(U117-Rout3-Pad11)") (class "Default")
      (node (ref "U117") (pin "11") (pinfunction "Rout3_11") (pintype "passive"))
    )
    (net (code "51") (name "unconnected-(U117-Rout4-Pad13)") (class "Default")
      (node (ref "U117") (pin "13") (pinfunction "Rout4_13") (pintype "passive"))
    )
  )
)
